# controller2_4.net
KiCad netlist of a schematic drawn in EAGLE
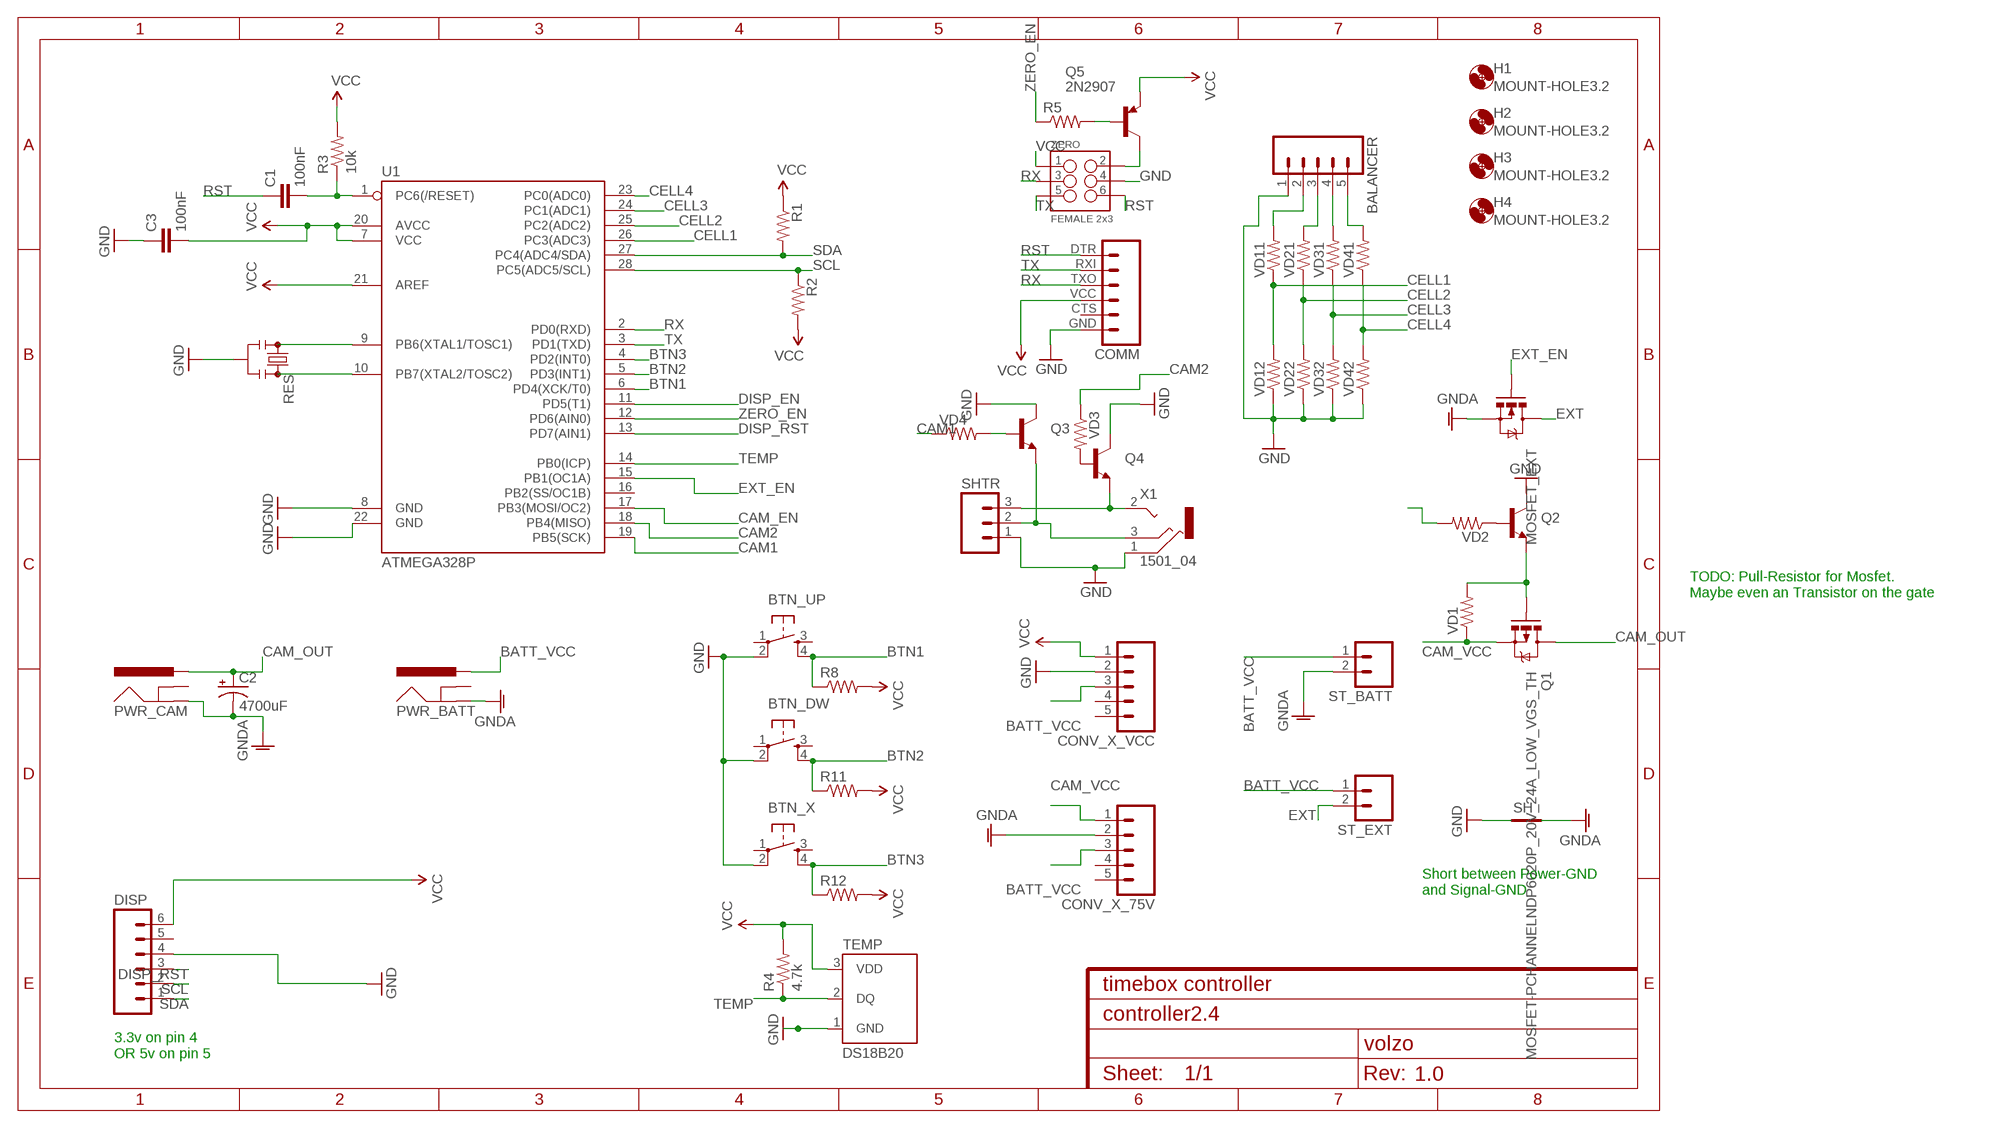
[diagram p0: schematic, sheet 1]

(export (version "E")
  (design (tool "Eeschema 10.0.6"))
  (components
    (comp (ref "BALANCER")
      (value "M05LOCK")
      (footprint "eagle-import:1X05_LOCK")
      (libsource (lib "eagle-import") (part "M05LOCK"))
    )
    (comp (ref "BTN_DW")
      (value "TAC_SWITCHPTH")
      (footprint "eagle-import:TACTILE-PTH")
      (libsource (lib "eagle-import") (part "TAC_SWITCHPTH"))
    )
    (comp (ref "BTN_UP")
      (value "TAC_SWITCHPTH")
      (footprint "eagle-import:TACTILE-PTH")
      (libsource (lib "eagle-import") (part "TAC_SWITCHPTH"))
    )
    (comp (ref "BTN_X")
      (value "TAC_SWITCHPTH")
      (footprint "eagle-import:TACTILE-PTH")
      (libsource (lib "eagle-import") (part "TAC_SWITCHPTH"))
    )
    (comp (ref "C1")
      (value "100nF")
      (footprint "eagle-import:CAP-PTH-SMALL")
      (libsource (lib "eagle-import") (part "CAPPTH"))
    )
    (comp (ref "C2")
      (value "4700uF")
      (footprint "eagle-import:CPOL-RADIAL-1000UF-63V")
      (libsource (lib "eagle-import") (part "CAP_POLPTH3"))
    )
    (comp (ref "C3")
      (value "100nF")
      (footprint "eagle-import:CAP-PTH-SMALL")
      (libsource (lib "eagle-import") (part "CAPPTH"))
    )
    (comp (ref "COMM")
      (value "FTDI_BASICPTH")
      (footprint "eagle-import:FTDI_BASIC")
      (libsource (lib "eagle-import") (part "FTDI_BASICPTH"))
    )
    (comp (ref "CONV_X_75V")
      (value "M05LOCK")
      (footprint "eagle-import:1X05_LOCK")
      (libsource (lib "eagle-import") (part "M05LOCK"))
    )
    (comp (ref "CONV_X_VCC")
      (value "M05LOCK")
      (footprint "eagle-import:1X05_LOCK")
      (libsource (lib "eagle-import") (part "M05LOCK"))
    )
    (comp (ref "DISP")
      (value "M06FEMALE_LOCK")
      (footprint "eagle-import:1X06_FEMALE_LOCK.010")
      (libsource (lib "eagle-import") (part "M06FEMALE_LOCK"))
    )
    (comp (ref "H1")
      (value "MOUNT-HOLE3.2")
      (footprint "eagle-import:3,2")
      (libsource (lib "eagle-import") (part "MOUNT-HOLE3.2"))
    )
    (comp (ref "H2")
      (value "MOUNT-HOLE3.2")
      (footprint "eagle-import:3,2")
      (libsource (lib "eagle-import") (part "MOUNT-HOLE3.2"))
    )
    (comp (ref "H3")
      (value "MOUNT-HOLE3.2")
      (footprint "eagle-import:3,2")
      (libsource (lib "eagle-import") (part "MOUNT-HOLE3.2"))
    )
    (comp (ref "H4")
      (value "MOUNT-HOLE3.2")
      (footprint "eagle-import:3,2")
      (libsource (lib "eagle-import") (part "MOUNT-HOLE3.2"))
    )
    (comp (ref "MOSFET_EXT")
      (value "MOSFET-NCHANNELFQP30N06L")
      (footprint "eagle-import:TO220V")
      (libsource (lib "eagle-import") (part "MOSFET-NCHANNELFQP30N06L"))
    )
    (comp (ref "PWR_BATT")
      (value "POWER_JACKPTH_BREAD")
      (footprint "eagle-import:POWER_JACK_PTH_BREAD")
      (libsource (lib "eagle-import") (part "POWER_JACKPTH_BREAD"))
    )
    (comp (ref "PWR_CAM")
      (value "POWER_JACKPTH_BREAD")
      (footprint "eagle-import:POWER_JACK_PTH_BREAD")
      (libsource (lib "eagle-import") (part "POWER_JACKPTH_BREAD"))
    )
    (comp (ref "Q1")
      (value "MOSFET-PCHANNELNDP6020P_20V_24A_LOW_VGS_TH")
      (footprint "eagle-import:TO220V")
      (libsource (lib "eagle-import") (part "MOSFET-PCHANNELNDP6020P_20V_24A_LOW_VGS_TH"))
    )
    (comp (ref "Q2")
      (value "TRANSISTOR_NPN2N3904")
      (footprint "eagle-import:TO-92")
      (libsource (lib "eagle-import") (part "TRANSISTOR_NPN2N3904"))
    )
    (comp (ref "Q3")
      (value "TRANSISTOR_NPN2N3904")
      (footprint "eagle-import:TO-92")
      (libsource (lib "eagle-import") (part "TRANSISTOR_NPN2N3904"))
    )
    (comp (ref "Q4")
      (value "TRANSISTOR_NPN2N3904")
      (footprint "eagle-import:TO-92")
      (libsource (lib "eagle-import") (part "TRANSISTOR_NPN2N3904"))
    )
    (comp (ref "Q5")
      (value "2N2907")
      (footprint "eagle-import:TO92-EBC-OVAL")
      (libsource (lib "eagle-import") (part "2N2907"))
    )
    (comp (ref "R1")
      (value "RESISTORAXIAL-0.3")
      (footprint "eagle-import:AXIAL-0.3")
      (libsource (lib "eagle-import") (part "RESISTORAXIAL-0.3"))
    )
    (comp (ref "R2")
      (value "RESISTORAXIAL-0.3")
      (footprint "eagle-import:AXIAL-0.3")
      (libsource (lib "eagle-import") (part "RESISTORAXIAL-0.3"))
    )
    (comp (ref "R3")
      (value "10k")
      (footprint "eagle-import:AXIAL-0.3")
      (libsource (lib "eagle-import") (part "RESISTORAXIAL-0.3"))
    )
    (comp (ref "R4")
      (value "4.7k")
      (footprint "eagle-import:AXIAL-0.3")
      (libsource (lib "eagle-import") (part "RESISTORAXIAL-0.3"))
    )
    (comp (ref "R5")
      (value "RESISTORAXIAL-0.3")
      (footprint "eagle-import:AXIAL-0.3")
      (libsource (lib "eagle-import") (part "RESISTORAXIAL-0.3"))
    )
    (comp (ref "R8")
      (value "RESISTORAXIAL-0.3")
      (footprint "eagle-import:AXIAL-0.3")
      (libsource (lib "eagle-import") (part "RESISTORAXIAL-0.3"))
    )
    (comp (ref "R11")
      (value "RESISTORAXIAL-0.3")
      (footprint "eagle-import:AXIAL-0.3")
      (libsource (lib "eagle-import") (part "RESISTORAXIAL-0.3"))
    )
    (comp (ref "R12")
      (value "RESISTORAXIAL-0.3")
      (footprint "eagle-import:AXIAL-0.3")
      (libsource (lib "eagle-import") (part "RESISTORAXIAL-0.3"))
    )
    (comp (ref "RES")
      (value "RESONATORPTH")
      (footprint "eagle-import:RESONATOR-PTH")
      (libsource (lib "eagle-import") (part "RESONATORPTH"))
    )
    (comp (ref "SH")
      (value "SHORT-HT5")
      (footprint "eagle-import:SHORT_TOP-50")
      (libsource (lib "eagle-import") (part "SHORT-HT5"))
    )
    (comp (ref "SHTR")
      (value "M03LOCK")
      (footprint "eagle-import:1X03_LOCK")
      (libsource (lib "eagle-import") (part "M03LOCK"))
    )
    (comp (ref "ST_BATT")
      (value "M025MM")
      (footprint "eagle-import:SCREWTERMINAL-5MM-2")
      (libsource (lib "eagle-import") (part "M025MM"))
    )
    (comp (ref "ST_EXT")
      (value "M025MM")
      (footprint "eagle-import:SCREWTERMINAL-5MM-2")
      (libsource (lib "eagle-import") (part "M025MM"))
    )
    (comp (ref "TEMP")
      (value "DS18B20")
      (footprint "eagle-import:TO-92-AMMO")
      (libsource (lib "eagle-import") (part "DS18B20"))
    )
    (comp (ref "U1")
      (value "ATMEGA328P")
      (footprint "eagle-import:DIL28-3")
      (libsource (lib "eagle-import") (part "ATMEGA328P_PDIP"))
    )
    (comp (ref "VD1")
      (value "RESISTORAXIAL-0.3")
      (footprint "eagle-import:AXIAL-0.3")
      (libsource (lib "eagle-import") (part "RESISTORAXIAL-0.3"))
    )
    (comp (ref "VD2")
      (value "RESISTORAXIAL-0.3")
      (footprint "eagle-import:AXIAL-0.3")
      (libsource (lib "eagle-import") (part "RESISTORAXIAL-0.3"))
    )
    (comp (ref "VD3")
      (value "RESISTORAXIAL-0.3")
      (footprint "eagle-import:AXIAL-0.3")
      (libsource (lib "eagle-import") (part "RESISTORAXIAL-0.3"))
    )
    (comp (ref "VD4")
      (value "RESISTORAXIAL-0.3")
      (footprint "eagle-import:AXIAL-0.3")
      (libsource (lib "eagle-import") (part "RESISTORAXIAL-0.3"))
    )
    (comp (ref "VD11")
      (value "RESISTORAXIAL-0.3")
      (footprint "eagle-import:AXIAL-0.3")
      (libsource (lib "eagle-import") (part "RESISTORAXIAL-0.3"))
    )
    (comp (ref "VD12")
      (value "RESISTORAXIAL-0.3")
      (footprint "eagle-import:AXIAL-0.3")
      (libsource (lib "eagle-import") (part "RESISTORAXIAL-0.3"))
    )
    (comp (ref "VD21")
      (value "RESISTORAXIAL-0.3")
      (footprint "eagle-import:AXIAL-0.3")
      (libsource (lib "eagle-import") (part "RESISTORAXIAL-0.3"))
    )
    (comp (ref "VD22")
      (value "RESISTORAXIAL-0.3")
      (footprint "eagle-import:AXIAL-0.3")
      (libsource (lib "eagle-import") (part "RESISTORAXIAL-0.3"))
    )
    (comp (ref "VD31")
      (value "RESISTORAXIAL-0.3")
      (footprint "eagle-import:AXIAL-0.3")
      (libsource (lib "eagle-import") (part "RESISTORAXIAL-0.3"))
    )
    (comp (ref "VD32")
      (value "RESISTORAXIAL-0.3")
      (footprint "eagle-import:AXIAL-0.3")
      (libsource (lib "eagle-import") (part "RESISTORAXIAL-0.3"))
    )
    (comp (ref "VD41")
      (value "RESISTORAXIAL-0.3")
      (footprint "eagle-import:AXIAL-0.3")
      (libsource (lib "eagle-import") (part "RESISTORAXIAL-0.3"))
    )
    (comp (ref "VD42")
      (value "RESISTORAXIAL-0.3")
      (footprint "eagle-import:AXIAL-0.3")
      (libsource (lib "eagle-import") (part "RESISTORAXIAL-0.3"))
    )
    (comp (ref "X1")
      (value "1501_04")
      (footprint "eagle-import:1501_05")
      (libsource (lib "eagle-import") (part "1501_04"))
    )
    (comp (ref "ZERO")
      (value "FEMALE 2x3")
      (footprint "eagle-import:2X3")
      (libsource (lib "eagle-import") (part "M03X2FEMALE"))
    )
  )
  (nets
    (net (code "1") (name "/BATT_VCC") (class "Default")
      (node (ref "CONV_X_75V") (pin "3") (pinfunction "3_3") (pintype "passive"))
      (node (ref "CONV_X_VCC") (pin "3") (pinfunction "3_3") (pintype "passive"))
      (node (ref "PWR_BATT") (pin "PWR") (pinfunction "PWR_PWR") (pintype "bidirectional"))
      (node (ref "ST_BATT") (pin "1") (pinfunction "1_1") (pintype "passive"))
      (node (ref "ST_EXT") (pin "1") (pinfunction "1_1") (pintype "passive"))
    )
    (net (code "2") (name "/BTN1") (class "Default")
      (node (ref "BTN_UP") (pin "4") (pinfunction "4_4") (pintype "passive"))
      (node (ref "R8") (pin "P$1") (pinfunction "1_P$1") (pintype "passive"))
      (node (ref "U1") (pin "6") (pinfunction "PD4(XCK/T0)_6") (pintype "bidirectional"))
    )
    (net (code "3") (name "/BTN2") (class "Default")
      (node (ref "BTN_DW") (pin "4") (pinfunction "4_4") (pintype "passive"))
      (node (ref "R11") (pin "P$1") (pinfunction "1_P$1") (pintype "passive"))
      (node (ref "U1") (pin "5") (pinfunction "PD3(INT1)_5") (pintype "bidirectional"))
    )
    (net (code "4") (name "/BTN3") (class "Default")
      (node (ref "BTN_X") (pin "4") (pinfunction "4_4") (pintype "passive"))
      (node (ref "R12") (pin "P$1") (pinfunction "1_P$1") (pintype "passive"))
      (node (ref "U1") (pin "4") (pinfunction "PD2(INT0)_4") (pintype "bidirectional"))
    )
    (net (code "5") (name "/CAM1") (class "Default")
      (node (ref "U1") (pin "19") (pinfunction "PB5(SCK)_19") (pintype "bidirectional"))
      (node (ref "VD4") (pin "P$1") (pinfunction "1_P$1") (pintype "passive"))
    )
    (net (code "6") (name "/CAM2") (class "Default")
      (node (ref "U1") (pin "18") (pinfunction "PB4(MISO)_18") (pintype "bidirectional"))
      (node (ref "VD3") (pin "P$1") (pinfunction "1_P$1") (pintype "passive"))
    )
    (net (code "7") (name "/CAM_EN") (class "Default")
      (node (ref "U1") (pin "17") (pinfunction "PB3(MOSI/OC2)_17") (pintype "bidirectional"))
      (node (ref "VD2") (pin "P$2") (pinfunction "2_P$2") (pintype "passive"))
    )
    (net (code "8") (name "/CAM_OUT") (class "Default")
      (node (ref "C2") (pin "1") (pinfunction "+_1") (pintype "passive"))
      (node (ref "PWR_CAM") (pin "PWR") (pinfunction "PWR_PWR") (pintype "bidirectional"))
      (node (ref "Q1") (pin "2") (pinfunction "D_2") (pintype "passive"))
    )
    (net (code "9") (name "/CAM_VCC") (class "Default")
      (node (ref "CONV_X_75V") (pin "1") (pinfunction "1_1") (pintype "passive"))
      (node (ref "Q1") (pin "3") (pinfunction "S_3") (pintype "passive"))
      (node (ref "VD1") (pin "P$1") (pinfunction "1_P$1") (pintype "passive"))
    )
    (net (code "10") (name "/CELL1") (class "Default")
      (node (ref "U1") (pin "26") (pinfunction "PC3(ADC3)_26") (pintype "bidirectional"))
      (node (ref "VD11") (pin "P$1") (pinfunction "1_P$1") (pintype "passive"))
      (node (ref "VD12") (pin "P$2") (pinfunction "2_P$2") (pintype "passive"))
    )
    (net (code "11") (name "/CELL2") (class "Default")
      (node (ref "U1") (pin "25") (pinfunction "PC2(ADC2)_25") (pintype "bidirectional"))
      (node (ref "VD21") (pin "P$1") (pinfunction "1_P$1") (pintype "passive"))
      (node (ref "VD22") (pin "P$2") (pinfunction "2_P$2") (pintype "passive"))
    )
    (net (code "12") (name "/CELL3") (class "Default")
      (node (ref "U1") (pin "24") (pinfunction "PC1(ADC1)_24") (pintype "bidirectional"))
      (node (ref "VD31") (pin "P$1") (pinfunction "1_P$1") (pintype "passive"))
      (node (ref "VD32") (pin "P$2") (pinfunction "2_P$2") (pintype "passive"))
    )
    (net (code "13") (name "/CELL4") (class "Default")
      (node (ref "U1") (pin "23") (pinfunction "PC0(ADC0)_23") (pintype "bidirectional"))
      (node (ref "VD41") (pin "P$1") (pinfunction "1_P$1") (pintype "passive"))
      (node (ref "VD42") (pin "P$2") (pinfunction "2_P$2") (pintype "passive"))
    )
    (net (code "14") (name "/DISP_EN") (class "Default")
      (node (ref "U1") (pin "11") (pinfunction "PD5(T1)_11") (pintype "bidirectional"))
    )
    (net (code "15") (name "/DISP_RST") (class "Default")
      (node (ref "DISP") (pin "3") (pinfunction "3_3") (pintype "passive"))
      (node (ref "U1") (pin "13") (pinfunction "PD7(AIN1)_13") (pintype "bidirectional"))
    )
    (net (code "16") (name "/EXT") (class "Default")
      (node (ref "MOSFET_EXT") (pin "2") (pinfunction "D_2") (pintype "passive"))
      (node (ref "ST_EXT") (pin "2") (pinfunction "2_2") (pintype "passive"))
    )
    (net (code "17") (name "/EXT_EN") (class "Default")
      (node (ref "MOSFET_EXT") (pin "1") (pinfunction "G_1") (pintype "passive"))
      (node (ref "U1") (pin "15") (pinfunction "PB1(OC1A)_15") (pintype "bidirectional"))
    )
    (net (code "18") (name "/RST") (class "Default")
      (node (ref "C1") (pin "1") (pinfunction "1_1") (pintype "passive"))
      (node (ref "COMM") (pin "DTR") (pinfunction "1_DTR") (pintype "passive"))
      (node (ref "ZERO") (pin "6") (pinfunction "6_6") (pintype "bidirectional"))
    )
    (net (code "19") (name "/RX") (class "Default")
      (node (ref "COMM") (pin "TXO") (pinfunction "3_TXO") (pintype "passive"))
      (node (ref "U1") (pin "2") (pinfunction "PD0(RXD)_2") (pintype "bidirectional"))
      (node (ref "ZERO") (pin "3") (pinfunction "3_3") (pintype "bidirectional"))
    )
    (net (code "20") (name "/SCL") (class "Default")
      (node (ref "DISP") (pin "2") (pinfunction "2_2") (pintype "passive"))
      (node (ref "R2") (pin "P$1") (pinfunction "1_P$1") (pintype "passive"))
      (node (ref "U1") (pin "28") (pinfunction "PC5(ADC5/SCL)_28") (pintype "bidirectional"))
    )
    (net (code "21") (name "/SDA") (class "Default")
      (node (ref "DISP") (pin "1") (pinfunction "1_1") (pintype "passive"))
      (node (ref "R1") (pin "P$2") (pinfunction "2_P$2") (pintype "passive"))
      (node (ref "U1") (pin "27") (pinfunction "PC4(ADC4/SDA)_27") (pintype "bidirectional"))
    )
    (net (code "22") (name "/TEMP") (class "Default")
      (node (ref "R4") (pin "P$1") (pinfunction "1_P$1") (pintype "passive"))
      (node (ref "TEMP") (pin "2") (pinfunction "DQ_2") (pintype "bidirectional"))
      (node (ref "U1") (pin "14") (pinfunction "PB0(ICP)_14") (pintype "bidirectional"))
    )
    (net (code "23") (name "/TX") (class "Default")
      (node (ref "COMM") (pin "RXI") (pinfunction "2_RXI") (pintype "passive"))
      (node (ref "U1") (pin "3") (pinfunction "PD1(TXD)_3") (pintype "bidirectional"))
      (node (ref "ZERO") (pin "5") (pinfunction "5_5") (pintype "bidirectional"))
    )
    (net (code "24") (name "/ZERO_EN") (class "Default")
      (node (ref "R5") (pin "P$1") (pinfunction "1_P$1") (pintype "passive"))
      (node (ref "U1") (pin "12") (pinfunction "PD6(AIN0)_12") (pintype "bidirectional"))
    )
    (net (code "25") (name "GND") (class "Default")
      (node (ref "BALANCER") (pin "1") (pinfunction "1_1") (pintype "passive"))
      (node (ref "BTN_DW") (pin "2") (pinfunction "2_2") (pintype "passive"))
      (node (ref "BTN_UP") (pin "2") (pinfunction "2_2") (pintype "passive"))
      (node (ref "BTN_X") (pin "2") (pinfunction "2_2") (pintype "passive"))
      (node (ref "C3") (pin "1") (pinfunction "1_1") (pintype "passive"))
      (node (ref "COMM") (pin "GND") (pinfunction "6_GND") (pintype "passive"))
      (node (ref "CONV_X_VCC") (pin "2") (pinfunction "2_2") (pintype "passive"))
      (node (ref "DISP") (pin "4") (pinfunction "4_4") (pintype "passive"))
      (node (ref "Q2") (pin "3") (pinfunction "C_3") (pintype "passive"))
      (node (ref "Q3") (pin "3") (pinfunction "C_3") (pintype "passive"))
      (node (ref "Q4") (pin "3") (pinfunction "C_3") (pintype "passive"))
      (node (ref "RES") (pin "2") (pinfunction "2_2") (pintype "passive"))
      (node (ref "SH") (pin "1") (pinfunction "P$1_1") (pintype "bidirectional"))
      (node (ref "SHTR") (pin "1") (pinfunction "1_1") (pintype "passive"))
      (node (ref "TEMP") (pin "1") (pinfunction "GND_1") (pintype "power_in"))
      (node (ref "U1") (pin "22") (pinfunction "GND_22") (pintype "bidirectional"))
      (node (ref "U1") (pin "8") (pinfunction "GND_8") (pintype "bidirectional"))
      (node (ref "VD12") (pin "P$1") (pinfunction "1_P$1") (pintype "passive"))
      (node (ref "VD22") (pin "P$1") (pinfunction "1_P$1") (pintype "passive"))
      (node (ref "VD32") (pin "P$1") (pinfunction "1_P$1") (pintype "passive"))
      (node (ref "VD42") (pin "P$1") (pinfunction "1_P$1") (pintype "passive"))
      (node (ref "X1") (pin "1") (pinfunction "1_1") (pintype "passive"))
      (node (ref "ZERO") (pin "4") (pinfunction "4_4") (pintype "bidirectional"))
    )
    (net (code "26") (name "GNDA") (class "Default")
      (node (ref "C2") (pin "2") (pinfunction "-_2") (pintype "passive"))
      (node (ref "CONV_X_75V") (pin "2") (pinfunction "2_2") (pintype "passive"))
      (node (ref "MOSFET_EXT") (pin "3") (pinfunction "S_3") (pintype "passive"))
      (node (ref "PWR_BATT") (pin "GND") (pinfunction "GND_GND") (pintype "bidirectional"))
      (node (ref "PWR_CAM") (pin "GND") (pinfunction "GND_GND") (pintype "bidirectional"))
      (node (ref "SH") (pin "2") (pinfunction "P$2_2") (pintype "bidirectional"))
      (node (ref "ST_BATT") (pin "2") (pinfunction "2_2") (pintype "passive"))
    )
    (net (code "27") (name "Net-(Q1-G)") (class "Default")
      (node (ref "Q1") (pin "1") (pinfunction "G_1") (pintype "passive"))
      (node (ref "Q2") (pin "1") (pinfunction "E_1") (pintype "passive"))
      (node (ref "VD1") (pin "P$2") (pinfunction "2_P$2") (pintype "passive"))
    )
    (net (code "28") (name "Net-(Q2-B)") (class "Default")
      (node (ref "Q2") (pin "2") (pinfunction "B_2") (pintype "passive"))
      (node (ref "VD2") (pin "P$1") (pinfunction "1_P$1") (pintype "passive"))
    )
    (net (code "29") (name "Net-(Q3-B)") (class "Default")
      (node (ref "Q3") (pin "2") (pinfunction "B_2") (pintype "passive"))
      (node (ref "VD4") (pin "P$2") (pinfunction "2_P$2") (pintype "passive"))
    )
    (net (code "30") (name "Net-(Q3-E)") (class "Default")
      (node (ref "Q3") (pin "1") (pinfunction "E_1") (pintype "passive"))
      (node (ref "SHTR") (pin "2") (pinfunction "2_2") (pintype "passive"))
      (node (ref "X1") (pin "3") (pinfunction "3_3") (pintype "passive"))
    )
    (net (code "31") (name "Net-(Q4-B)") (class "Default")
      (node (ref "Q4") (pin "2") (pinfunction "B_2") (pintype "passive"))
      (node (ref "VD3") (pin "P$2") (pinfunction "2_P$2") (pintype "passive"))
    )
    (net (code "32") (name "Net-(Q4-E)") (class "Default")
      (node (ref "Q4") (pin "1") (pinfunction "E_1") (pintype "passive"))
      (node (ref "SHTR") (pin "3") (pinfunction "3_3") (pintype "passive"))
      (node (ref "X1") (pin "2") (pinfunction "2_2") (pintype "passive"))
    )
    (net (code "33") (name "Net-(Q5-PadC)") (class "Default")
      (node (ref "Q5") (pin "C") (pinfunction "C_C") (pintype "passive"))
      (node (ref "ZERO") (pin "2") (pinfunction "2_2") (pintype "bidirectional"))
    )
    (net (code "34") (name "Net-(R3-1)") (class "Default")
      (node (ref "C1") (pin "2") (pinfunction "2_2") (pintype "passive"))
      (node (ref "R3") (pin "P$1") (pinfunction "1_P$1") (pintype "passive"))
      (node (ref "U1") (pin "1") (pinfunction "PC6(/RESET)_1") (pintype "bidirectional"))
    )
    (net (code "35") (name "Net-(R5-2)") (class "Default")
      (node (ref "Q5") (pin "B") (pinfunction "B_B") (pintype "passive"))
      (node (ref "R5") (pin "P$2") (pinfunction "2_P$2") (pintype "passive"))
    )
    (net (code "36") (name "Net-(U1-PB6(XTAL1{slash}TOSC1))") (class "Default")
      (node (ref "RES") (pin "1") (pinfunction "1_1") (pintype "passive"))
      (node (ref "U1") (pin "9") (pinfunction "PB6(XTAL1/TOSC1)_9") (pintype "bidirectional"))
    )
    (net (code "37") (name "Net-(U1-PB7(XTAL2{slash}TOSC2))") (class "Default")
      (node (ref "RES") (pin "3") (pinfunction "3_3") (pintype "passive"))
      (node (ref "U1") (pin "10") (pinfunction "PB7(XTAL2/TOSC2)_10") (pintype "bidirectional"))
    )
    (net (code "38") (name "Net-(VD11-2)") (class "Default")
      (node (ref "BALANCER") (pin "2") (pinfunction "2_2") (pintype "passive"))
      (node (ref "VD11") (pin "P$2") (pinfunction "2_P$2") (pintype "passive"))
    )
    (net (code "39") (name "Net-(VD21-2)") (class "Default")
      (node (ref "BALANCER") (pin "3") (pinfunction "3_3") (pintype "passive"))
      (node (ref "VD21") (pin "P$2") (pinfunction "2_P$2") (pintype "passive"))
    )
    (net (code "40") (name "Net-(VD31-2)") (class "Default")
      (node (ref "BALANCER") (pin "4") (pinfunction "4_4") (pintype "passive"))
      (node (ref "VD31") (pin "P$2") (pinfunction "2_P$2") (pintype "passive"))
    )
    (net (code "41") (name "Net-(VD41-2)") (class "Default")
      (node (ref "BALANCER") (pin "5") (pinfunction "5_5") (pintype "passive"))
      (node (ref "VD41") (pin "P$2") (pinfunction "2_P$2") (pintype "passive"))
    )
    (net (code "42") (name "VCC") (class "Default")
      (node (ref "C3") (pin "2") (pinfunction "2_2") (pintype "passive"))
      (node (ref "COMM") (pin "VCC") (pinfunction "4_VCC") (pintype "passive"))
      (node (ref "CONV_X_VCC") (pin "1") (pinfunction "1_1") (pintype "passive"))
      (node (ref "DISP") (pin "6") (pinfunction "6_6") (pintype "passive"))
      (node (ref "Q5") (pin "E") (pinfunction "E_E") (pintype "passive"))
      (node (ref "R1") (pin "P$1") (pinfunction "1_P$1") (pintype "passive"))
      (node (ref "R11") (pin "P$2") (pinfunction "2_P$2") (pintype "passive"))
      (node (ref "R12") (pin "P$2") (pinfunction "2_P$2") (pintype "passive"))
      (node (ref "R2") (pin "P$2") (pinfunction "2_P$2") (pintype "passive"))
      (node (ref "R3") (pin "P$2") (pinfunction "2_P$2") (pintype "passive"))
      (node (ref "R4") (pin "P$2") (pinfunction "2_P$2") (pintype "passive"))
      (node (ref "R8") (pin "P$2") (pinfunction "2_P$2") (pintype "passive"))
      (node (ref "TEMP") (pin "3") (pinfunction "VDD_3") (pintype "power_in"))
      (node (ref "U1") (pin "20") (pinfunction "AVCC_20") (pintype "bidirectional"))
      (node (ref "U1") (pin "21") (pinfunction "AREF_21") (pintype "bidirectional"))
      (node (ref "U1") (pin "7") (pinfunction "VCC_7") (pintype "bidirectional"))
      (node (ref "ZERO") (pin "1") (pinfunction "1_1") (pintype "bidirectional"))
    )
    (net (code "43") (name "unconnected-(BTN_DW-Pad1)") (class "Default")
      (node (ref "BTN_DW") (pin "1") (pinfunction "1_1") (pintype "passive"))
    )
    (net (code "44") (name "unconnected-(BTN_DW-Pad3)") (class "Default")
      (node (ref "BTN_DW") (pin "3") (pinfunction "3_3") (pintype "passive"))
    )
    (net (code "45") (name "unconnected-(BTN_UP-Pad1)") (class "Default")
      (node (ref "BTN_UP") (pin "1") (pinfunction "1_1") (pintype "passive"))
    )
    (net (code "46") (name "unconnected-(BTN_UP-Pad3)") (class "Default")
      (node (ref "BTN_UP") (pin "3") (pinfunction "3_3") (pintype "passive"))
    )
    (net (code "47") (name "unconnected-(BTN_X-Pad1)") (class "Default")
      (node (ref "BTN_X") (pin "1") (pinfunction "1_1") (pintype "passive"))
    )
    (net (code "48") (name "unconnected-(BTN_X-Pad3)") (class "Default")
      (node (ref "BTN_X") (pin "3") (pinfunction "3_3") (pintype "passive"))
    )
    (net (code "49") (name "unconnected-(COMM-5-PadCTS)") (class "Default")
      (node (ref "COMM") (pin "CTS") (pinfunction "5_CTS") (pintype "passive"))
    )
    (net (code "50") (name "unconnected-(CONV_X_75V-Pad4)") (class "Default")
      (node (ref "CONV_X_75V") (pin "4") (pinfunction "4_4") (pintype "passive"))
    )
    (net (code "51") (name "unconnected-(CONV_X_75V-Pad5)") (class "Default")
      (node (ref "CONV_X_75V") (pin "5") (pinfunction "5_5") (pintype "passive"))
    )
    (net (code "52") (name "unconnected-(CONV_X_VCC-Pad4)") (class "Default")
      (node (ref "CONV_X_VCC") (pin "4") (pinfunction "4_4") (pintype "passive"))
    )
    (net (code "53") (name "unconnected-(CONV_X_VCC-Pad5)") (class "Default")
      (node (ref "CONV_X_VCC") (pin "5") (pinfunction "5_5") (pintype "passive"))
    )
    (net (code "54") (name "unconnected-(DISP-Pad5)") (class "Default")
      (node (ref "DISP") (pin "5") (pinfunction "5_5") (pintype "passive"))
    )
    (net (code "55") (name "unconnected-(PWR_BATT-PadGNDBREAK)") (class "Default")
      (node (ref "PWR_BATT") (pin "GNDBREAK") (pinfunction "GNDBREAK_GNDBREAK") (pintype "bidirectional"))
    )
    (net (code "56") (name "unconnected-(PWR_CAM-PadGNDBREAK)") (class "Default")
      (node (ref "PWR_CAM") (pin "GNDBREAK") (pinfunction "GNDBREAK_GNDBREAK") (pintype "bidirectional"))
    )
    (net (code "57") (name "unconnected-(U1-PB2(SS{slash}OC1B)-Pad16)") (class "Default")
      (node (ref "U1") (pin "16") (pinfunction "PB2(SS/OC1B)_16") (pintype "bidirectional"))
    )
  )
)
